# board.net
KiCad netlist of a schematic drawn in EAGLE
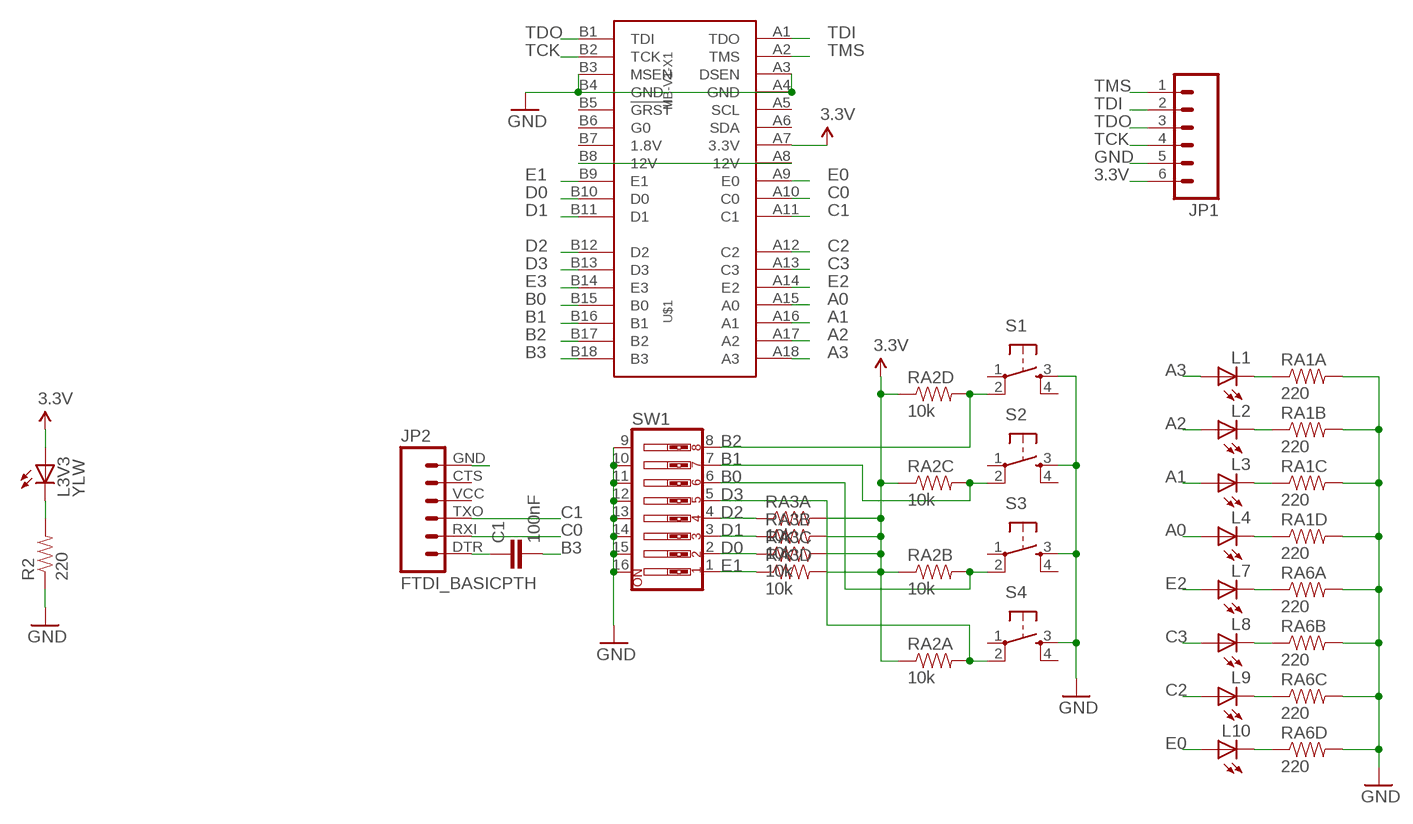
[diagram p0: schematic, sheet 1]

(export (version "E")
  (design (tool "Eeschema 10.0.6"))
  (components
    (comp (ref "C1")
      (value "100nF")
      (footprint "eagle-import:0402-CAP")
      (libsource (lib "eagle-import") (part "CAP0402-CAP"))
    )
    (comp (ref "JP1")
      (value "M06LOCK")
      (footprint "eagle-import:1X06_LOCK")
      (libsource (lib "eagle-import") (part "M06LOCK"))
    )
    (comp (ref "JP2")
      (value "FTDI_BASICPTH")
      (footprint "eagle-import:FTDI_BASIC")
      (libsource (lib "eagle-import") (part "FTDI_BASICPTH"))
    )
    (comp (ref "L1")
      (value "LED0603")
      (footprint "eagle-import:0603_LED")
      (libsource (lib "eagle-import") (part "LED0603"))
    )
    (comp (ref "L2")
      (value "LED0603")
      (footprint "eagle-import:0603_LED")
      (libsource (lib "eagle-import") (part "LED0603"))
    )
    (comp (ref "L3")
      (value "LED0603")
      (footprint "eagle-import:0603_LED")
      (libsource (lib "eagle-import") (part "LED0603"))
    )
    (comp (ref "L3V3")
      (value "YLW")
      (footprint "eagle-import:0603_LED")
      (libsource (lib "eagle-import") (part "LED0603"))
    )
    (comp (ref "L4")
      (value "LED0603")
      (footprint "eagle-import:0603_LED")
      (libsource (lib "eagle-import") (part "LED0603"))
    )
    (comp (ref "L7")
      (value "LED0603")
      (footprint "eagle-import:0603_LED")
      (libsource (lib "eagle-import") (part "LED0603"))
    )
    (comp (ref "L8")
      (value "LED0603")
      (footprint "eagle-import:0603_LED")
      (libsource (lib "eagle-import") (part "LED0603"))
    )
    (comp (ref "L9")
      (value "LED0603")
      (footprint "eagle-import:0603_LED")
      (libsource (lib "eagle-import") (part "LED0603"))
    )
    (comp (ref "L10")
      (value "LED0603")
      (footprint "eagle-import:0603_LED")
      (libsource (lib "eagle-import") (part "LED0603"))
    )
    (comp (ref "R2")
      (value "220")
      (footprint "eagle-import:0603-RES")
      (libsource (lib "eagle-import") (part "RESISTOR0603"))
    )
    (comp (ref "RA1")
      (value "220")
      (footprint "eagle-import:0603-ARV")
      (libsource (lib "eagle-import") (part "RESISTOR_ARRAY0603_X4"))
    )
    (comp (ref "RA2")
      (value "10k")
      (footprint "eagle-import:0603-ARV")
      (libsource (lib "eagle-import") (part "RESISTOR_ARRAY0603_X4"))
    )
    (comp (ref "RA3")
      (value "10k")
      (footprint "eagle-import:0603-ARV")
      (libsource (lib "eagle-import") (part "RESISTOR_ARRAY0603_X4"))
    )
    (comp (ref "RA6")
      (value "220")
      (footprint "eagle-import:0603-ARV")
      (libsource (lib "eagle-import") (part "RESISTOR_ARRAY0603_X4"))
    )
    (comp (ref "S1")
      (value "TAC_SWITCHPTH")
      (footprint "eagle-import:TACTILE-PTH")
      (libsource (lib "eagle-import") (part "TAC_SWITCHPTH"))
    )
    (comp (ref "S2")
      (value "TAC_SWITCHPTH")
      (footprint "eagle-import:TACTILE-PTH")
      (libsource (lib "eagle-import") (part "TAC_SWITCHPTH"))
    )
    (comp (ref "S3")
      (value "TAC_SWITCHPTH")
      (footprint "eagle-import:TACTILE-PTH")
      (libsource (lib "eagle-import") (part "TAC_SWITCHPTH"))
    )
    (comp (ref "S4")
      (value "TAC_SWITCHPTH")
      (footprint "eagle-import:TACTILE-PTH")
      (libsource (lib "eagle-import") (part "TAC_SWITCHPTH"))
    )
    (comp (ref "SW1")
      (value "SW_DIP-8")
      (footprint "eagle-import:DIPSWITCH-08")
      (libsource (lib "eagle-import") (part "SW_DIP-8"))
    )
    (comp (ref "U$1")
      (value "MB-V1-X1")
      (footprint "eagle-import:PCIE-X1-EDGE")
      (libsource (lib "eagle-import") (part "MB-V1-X1"))
    )
  )
  (nets
    (net (code "1") (name "/A0") (class "Default")
      (node (ref "L4") (pin "A") (pinfunction "A_A") (pintype "passive"))
      (node (ref "U$1") (pin "A15") (pinfunction "A0_A15") (pintype "bidirectional"))
    )
    (net (code "2") (name "/A1") (class "Default")
      (node (ref "L3") (pin "A") (pinfunction "A_A") (pintype "passive"))
      (node (ref "U$1") (pin "A16") (pinfunction "A1_A16") (pintype "bidirectional"))
    )
    (net (code "3") (name "/A2") (class "Default")
      (node (ref "L2") (pin "A") (pinfunction "A_A") (pintype "passive"))
      (node (ref "U$1") (pin "A17") (pinfunction "A2_A17") (pintype "bidirectional"))
    )
    (net (code "4") (name "/A3") (class "Default")
      (node (ref "L1") (pin "A") (pinfunction "A_A") (pintype "passive"))
      (node (ref "U$1") (pin "A18") (pinfunction "A3_A18") (pintype "bidirectional"))
    )
    (net (code "5") (name "/B0") (class "Default")
      (node (ref "RA2") (pin "7") (pinfunction "2_7") (pintype "passive"))
      (node (ref "S3") (pin "2") (pinfunction "2_2") (pintype "passive"))
      (node (ref "SW1") (pin "6") (pinfunction "6_6") (pintype "passive"))
      (node (ref "U$1") (pin "B15") (pinfunction "B0_B15") (pintype "bidirectional"))
    )
    (net (code "6") (name "/B1") (class "Default")
      (node (ref "RA2") (pin "6") (pinfunction "2_6") (pintype "passive"))
      (node (ref "S2") (pin "2") (pinfunction "2_2") (pintype "passive"))
      (node (ref "SW1") (pin "7") (pinfunction "7_7") (pintype "passive"))
      (node (ref "U$1") (pin "B16") (pinfunction "B1_B16") (pintype "bidirectional"))
    )
    (net (code "7") (name "/B2") (class "Default")
      (node (ref "RA2") (pin "5") (pinfunction "2_5") (pintype "passive"))
      (node (ref "S1") (pin "2") (pinfunction "2_2") (pintype "passive"))
      (node (ref "SW1") (pin "8") (pinfunction "8_8") (pintype "passive"))
      (node (ref "U$1") (pin "B17") (pinfunction "B2_B17") (pintype "bidirectional"))
    )
    (net (code "8") (name "/B3") (class "Default")
      (node (ref "C1") (pin "2") (pinfunction "2_2") (pintype "passive"))
      (node (ref "U$1") (pin "B18") (pinfunction "B3_B18") (pintype "bidirectional"))
    )
    (net (code "9") (name "/C0") (class "Default")
      (node (ref "JP2") (pin "RXI") (pinfunction "2_RXI") (pintype "passive"))
      (node (ref "U$1") (pin "A10") (pinfunction "C0_A10") (pintype "bidirectional"))
    )
    (net (code "10") (name "/C1") (class "Default")
      (node (ref "JP2") (pin "TXO") (pinfunction "3_TXO") (pintype "passive"))
      (node (ref "U$1") (pin "A11") (pinfunction "C1_A11") (pintype "bidirectional"))
    )
    (net (code "11") (name "/C2") (class "Default")
      (node (ref "L9") (pin "A") (pinfunction "A_A") (pintype "passive"))
      (node (ref "U$1") (pin "A12") (pinfunction "C2_A12") (pintype "bidirectional"))
    )
    (net (code "12") (name "/C3") (class "Default")
      (node (ref "L8") (pin "A") (pinfunction "A_A") (pintype "passive"))
      (node (ref "U$1") (pin "A13") (pinfunction "C3_A13") (pintype "bidirectional"))
    )
    (net (code "13") (name "/D0") (class "Default")
      (node (ref "RA3") (pin "3") (pinfunction "1_3") (pintype "passive"))
      (node (ref "SW1") (pin "2") (pinfunction "2_2") (pintype "passive"))
      (node (ref "U$1") (pin "B10") (pinfunction "D0_B10") (pintype "bidirectional"))
    )
    (net (code "14") (name "/D1") (class "Default")
      (node (ref "RA3") (pin "2") (pinfunction "1_2") (pintype "passive"))
      (node (ref "SW1") (pin "3") (pinfunction "3_3") (pintype "passive"))
      (node (ref "U$1") (pin "B11") (pinfunction "D1_B11") (pintype "bidirectional"))
    )
    (net (code "15") (name "/D2") (class "Default")
      (node (ref "RA3") (pin "1") (pinfunction "1_1") (pintype "passive"))
      (node (ref "SW1") (pin "4") (pinfunction "4_4") (pintype "passive"))
      (node (ref "U$1") (pin "B12") (pinfunction "D2_B12") (pintype "bidirectional"))
    )
    (net (code "16") (name "/D3") (class "Default")
      (node (ref "RA2") (pin "8") (pinfunction "2_8") (pintype "passive"))
      (node (ref "S4") (pin "2") (pinfunction "2_2") (pintype "passive"))
      (node (ref "SW1") (pin "5") (pinfunction "5_5") (pintype "passive"))
      (node (ref "U$1") (pin "B13") (pinfunction "D3_B13") (pintype "bidirectional"))
    )
    (net (code "17") (name "/E0") (class "Default")
      (node (ref "L10") (pin "A") (pinfunction "A_A") (pintype "passive"))
      (node (ref "U$1") (pin "A9") (pinfunction "E0_A9") (pintype "bidirectional"))
    )
    (net (code "18") (name "/E1") (class "Default")
      (node (ref "RA3") (pin "4") (pinfunction "1_4") (pintype "passive"))
      (node (ref "SW1") (pin "1") (pinfunction "1_1") (pintype "passive"))
      (node (ref "U$1") (pin "B9") (pinfunction "E1_B9") (pintype "bidirectional"))
    )
    (net (code "19") (name "/E2") (class "Default")
      (node (ref "L7") (pin "A") (pinfunction "A_A") (pintype "passive"))
      (node (ref "U$1") (pin "A14") (pinfunction "E2_A14") (pintype "bidirectional"))
    )
    (net (code "20") (name "/E3") (class "Default")
      (node (ref "U$1") (pin "B14") (pinfunction "E3_B14") (pintype "bidirectional"))
    )
    (net (code "21") (name "/TCK") (class "Default")
      (node (ref "JP1") (pin "4") (pinfunction "4_4") (pintype "passive"))
      (node (ref "U$1") (pin "B2") (pinfunction "TCK_B2") (pintype "bidirectional"))
    )
    (net (code "22") (name "/TDI") (class "Default")
      (node (ref "JP1") (pin "2") (pinfunction "2_2") (pintype "passive"))
      (node (ref "U$1") (pin "A1") (pinfunction "TDO_A1") (pintype "bidirectional"))
    )
    (net (code "23") (name "/TDO") (class "Default")
      (node (ref "JP1") (pin "3") (pinfunction "3_3") (pintype "passive"))
      (node (ref "U$1") (pin "B1") (pinfunction "TDI_B1") (pintype "bidirectional"))
    )
    (net (code "24") (name "/TMS") (class "Default")
      (node (ref "JP1") (pin "1") (pinfunction "1_1") (pintype "passive"))
      (node (ref "U$1") (pin "A2") (pinfunction "TMS_A2") (pintype "bidirectional"))
    )
    (net (code "25") (name "3.3V") (class "Default")
      (node (ref "JP1") (pin "6") (pinfunction "6_6") (pintype "passive"))
      (node (ref "L3V3") (pin "A") (pinfunction "A_A") (pintype "passive"))
      (node (ref "RA2") (pin "1") (pinfunction "1_1") (pintype "passive"))
      (node (ref "RA2") (pin "2") (pinfunction "1_2") (pintype "passive"))
      (node (ref "RA2") (pin "3") (pinfunction "1_3") (pintype "passive"))
      (node (ref "RA2") (pin "4") (pinfunction "1_4") (pintype "passive"))
      (node (ref "RA3") (pin "5") (pinfunction "2_5") (pintype "passive"))
      (node (ref "RA3") (pin "6") (pinfunction "2_6") (pintype "passive"))
      (node (ref "RA3") (pin "7") (pinfunction "2_7") (pintype "passive"))
      (node (ref "RA3") (pin "8") (pinfunction "2_8") (pintype "passive"))
      (node (ref "U$1") (pin "A7") (pinfunction "3.3V_A7") (pintype "bidirectional"))
    )
    (net (code "26") (name "GND") (class "Default")
      (node (ref "JP1") (pin "5") (pinfunction "5_5") (pintype "passive"))
      (node (ref "JP2") (pin "GND") (pinfunction "6_GND") (pintype "passive"))
      (node (ref "R2") (pin "1") (pinfunction "1_1") (pintype "passive"))
      (node (ref "RA1") (pin "5") (pinfunction "2_5") (pintype "passive"))
      (node (ref "RA1") (pin "6") (pinfunction "2_6") (pintype "passive"))
      (node (ref "RA1") (pin "7") (pinfunction "2_7") (pintype "passive"))
      (node (ref "RA1") (pin "8") (pinfunction "2_8") (pintype "passive"))
      (node (ref "RA6") (pin "5") (pinfunction "2_5") (pintype "passive"))
      (node (ref "RA6") (pin "6") (pinfunction "2_6") (pintype "passive"))
      (node (ref "RA6") (pin "7") (pinfunction "2_7") (pintype "passive"))
      (node (ref "RA6") (pin "8") (pinfunction "2_8") (pintype "passive"))
      (node (ref "S1") (pin "3") (pinfunction "3_3") (pintype "passive"))
      (node (ref "S2") (pin "3") (pinfunction "3_3") (pintype "passive"))
      (node (ref "S3") (pin "3") (pinfunction "3_3") (pintype "passive"))
      (node (ref "S4") (pin "3") (pinfunction "3_3") (pintype "passive"))
      (node (ref "SW1") (pin "10") (pinfunction "10_10") (pintype "passive"))
      (node (ref "SW1") (pin "11") (pinfunction "11_11") (pintype "passive"))
      (node (ref "SW1") (pin "12") (pinfunction "12_12") (pintype "passive"))
      (node (ref "SW1") (pin "13") (pinfunction "13_13") (pintype "passive"))
      (node (ref "SW1") (pin "14") (pinfunction "14_14") (pintype "passive"))
      (node (ref "SW1") (pin "15") (pinfunction "15_15") (pintype "passive"))
      (node (ref "SW1") (pin "16") (pinfunction "16_16") (pintype "passive"))
      (node (ref "SW1") (pin "9") (pinfunction "9_9") (pintype "passive"))
      (node (ref "U$1") (pin "A3") (pinfunction "DSEN_A3") (pintype "bidirectional"))
      (node (ref "U$1") (pin "A4") (pinfunction "GND_A4") (pintype "bidirectional"))
      (node (ref "U$1") (pin "B3") (pinfunction "MSEN_B3") (pintype "bidirectional"))
      (node (ref "U$1") (pin "B4") (pinfunction "GND_B4") (pintype "bidirectional"))
    )
    (net (code "27") (name "Net-(JP2-1)") (class "Default")
      (node (ref "C1") (pin "1") (pinfunction "1_1") (pintype "passive"))
      (node (ref "JP2") (pin "DTR") (pinfunction "1_DTR") (pintype "passive"))
    )
    (net (code "28") (name "Net-(L1-PadC)") (class "Default")
      (node (ref "L1") (pin "C") (pinfunction "C_C") (pintype "passive"))
      (node (ref "RA1") (pin "1") (pinfunction "1_1") (pintype "passive"))
    )
    (net (code "29") (name "Net-(L3V3-PadC)") (class "Default")
      (node (ref "L3V3") (pin "C") (pinfunction "C_C") (pintype "passive"))
      (node (ref "R2") (pin "2") (pinfunction "2_2") (pintype "passive"))
    )
    (net (code "30") (name "Net-(L7-PadC)") (class "Default")
      (node (ref "L7") (pin "C") (pinfunction "C_C") (pintype "passive"))
      (node (ref "RA6") (pin "1") (pinfunction "1_1") (pintype "passive"))
    )
    (net (code "31") (name "Net-(RA1B-1)") (class "Default")
      (node (ref "L2") (pin "C") (pinfunction "C_C") (pintype "passive"))
      (node (ref "RA1") (pin "2") (pinfunction "1_2") (pintype "passive"))
    )
    (net (code "32") (name "Net-(RA1C-1)") (class "Default")
      (node (ref "L3") (pin "C") (pinfunction "C_C") (pintype "passive"))
      (node (ref "RA1") (pin "3") (pinfunction "1_3") (pintype "passive"))
    )
    (net (code "33") (name "Net-(RA1D-1)") (class "Default")
      (node (ref "L4") (pin "C") (pinfunction "C_C") (pintype "passive"))
      (node (ref "RA1") (pin "4") (pinfunction "1_4") (pintype "passive"))
    )
    (net (code "34") (name "Net-(RA6B-1)") (class "Default")
      (node (ref "L8") (pin "C") (pinfunction "C_C") (pintype "passive"))
      (node (ref "RA6") (pin "2") (pinfunction "1_2") (pintype "passive"))
    )
    (net (code "35") (name "Net-(RA6C-1)") (class "Default")
      (node (ref "L9") (pin "C") (pinfunction "C_C") (pintype "passive"))
      (node (ref "RA6") (pin "3") (pinfunction "1_3") (pintype "passive"))
    )
    (net (code "36") (name "Net-(RA6D-1)") (class "Default")
      (node (ref "L10") (pin "C") (pinfunction "C_C") (pintype "passive"))
      (node (ref "RA6") (pin "4") (pinfunction "1_4") (pintype "passive"))
    )
    (net (code "37") (name "Net-(U$1-12V-PadA8)") (class "Default")
      (node (ref "U$1") (pin "A8") (pinfunction "12V_A8") (pintype "bidirectional"))
      (node (ref "U$1") (pin "B8") (pinfunction "12V_B8") (pintype "bidirectional"))
    )
    (net (code "38") (name "unconnected-(JP2-4-PadVCC)") (class "Default")
      (node (ref "JP2") (pin "VCC") (pinfunction "4_VCC") (pintype "passive"))
    )
    (net (code "39") (name "unconnected-(JP2-5-PadCTS)") (class "Default")
      (node (ref "JP2") (pin "CTS") (pinfunction "5_CTS") (pintype "passive"))
    )
    (net (code "40") (name "unconnected-(S1-Pad1)") (class "Default")
      (node (ref "S1") (pin "1") (pinfunction "1_1") (pintype "passive"))
    )
    (net (code "41") (name "unconnected-(S1-Pad4)") (class "Default")
      (node (ref "S1") (pin "4") (pinfunction "4_4") (pintype "passive"))
    )
    (net (code "42") (name "unconnected-(S2-Pad1)") (class "Default")
      (node (ref "S2") (pin "1") (pinfunction "1_1") (pintype "passive"))
    )
    (net (code "43") (name "unconnected-(S2-Pad4)") (class "Default")
      (node (ref "S2") (pin "4") (pinfunction "4_4") (pintype "passive"))
    )
    (net (code "44") (name "unconnected-(S3-Pad1)") (class "Default")
      (node (ref "S3") (pin "1") (pinfunction "1_1") (pintype "passive"))
    )
    (net (code "45") (name "unconnected-(S3-Pad4)") (class "Default")
      (node (ref "S3") (pin "4") (pinfunction "4_4") (pintype "passive"))
    )
    (net (code "46") (name "unconnected-(S4-Pad1)") (class "Default")
      (node (ref "S4") (pin "1") (pinfunction "1_1") (pintype "passive"))
    )
    (net (code "47") (name "unconnected-(S4-Pad4)") (class "Default")
      (node (ref "S4") (pin "4") (pinfunction "4_4") (pintype "passive"))
    )
    (net (code "48") (name "unconnected-(U$1-1.8V-PadB7)") (class "Default")
      (node (ref "U$1") (pin "B7") (pinfunction "1.8V_B7") (pintype "bidirectional"))
    )
    (net (code "49") (name "unconnected-(U$1-G0-PadB6)") (class "Default")
      (node (ref "U$1") (pin "B6") (pinfunction "G0_B6") (pintype "bidirectional"))
    )
    (net (code "50") (name "unconnected-(U$1-SCL-PadA5)") (class "Default")
      (node (ref "U$1") (pin "A5") (pinfunction "SCL_A5") (pintype "bidirectional"))
    )
    (net (code "51") (name "unconnected-(U$1-SDA-PadA6)") (class "Default")
      (node (ref "U$1") (pin "A6") (pinfunction "SDA_A6") (pintype "bidirectional"))
    )
    (net (code "52") (name "unconnected-(U$1-~{GRST}-PadB5)") (class "Default")
      (node (ref "U$1") (pin "B5") (pinfunction "~{GRST}_B5") (pintype "bidirectional"))
    )
  )
)
